# schimmeliger_keller.net
KiCad netlist of a schematic drawn in EAGLE
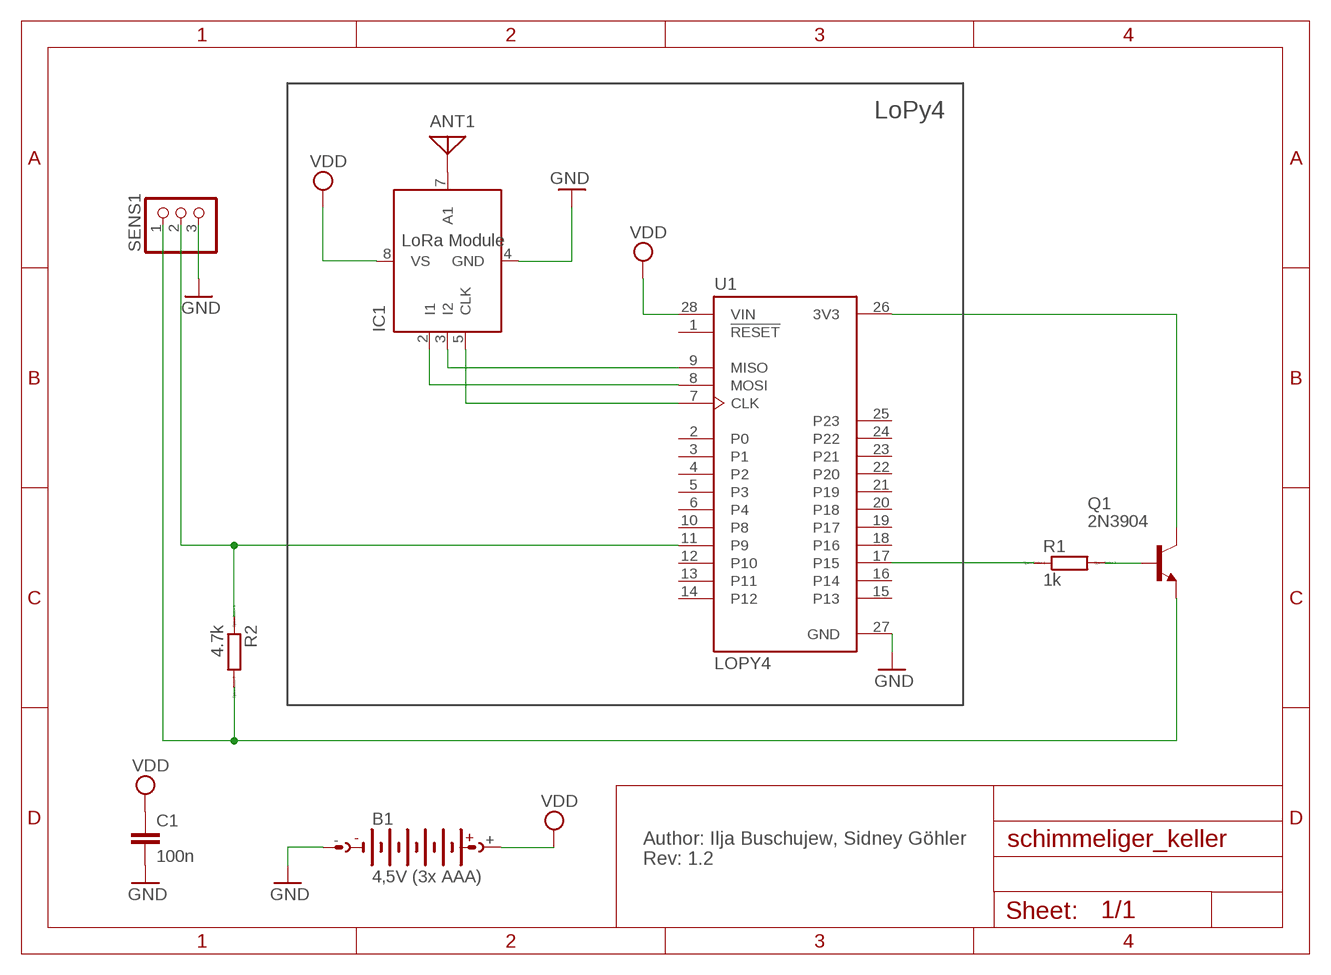
[diagram p0: schematic, sheet 1]

(export (version "E")
  (design (tool "Eeschema 10.0.6"))
  (components
    (comp (ref "ANT1")
      (value "ANTENNA")
      (footprint "eagle-import:PAD-01")
      (libsource (lib "eagle-import") (part "ANTENNA"))
    )
    (comp (ref "B1")
      (value "4,5V (3x AAA)")
      (footprint "eagle-import:AB9V")
      (libsource (lib "eagle-import") (part "AB9V"))
    )
    (comp (ref "C1")
      (value "100n")
      (footprint "eagle-import:C10B4")
      (libsource (lib "eagle-import") (part "C10/4"))
    )
    (comp (ref "IC1")
      (value "LoRa Module")
      (footprint "eagle-import:DIL08")
      (libsource (lib "eagle-import") (part "U893BSE"))
    )
    (comp (ref "Q1")
      (value "2N3904")
      (footprint "eagle-import:TO92")
      (libsource (lib "eagle-import") (part "2N3904"))
    )
    (comp (ref "R1")
      (value "1k")
      (footprint "eagle-import:0204_7")
      (libsource (lib "eagle-import") (part "R0204/7"))
    )
    (comp (ref "R2")
      (value "4.7k")
      (footprint "eagle-import:0204_7")
      (libsource (lib "eagle-import") (part "R0204/7"))
    )
    (comp (ref "SENS1")
      (value "PINHD-1X3")
      (footprint "eagle-import:1X03")
      (libsource (lib "eagle-import") (part "PINHD-1X3"))
    )
    (comp (ref "U1")
      (value "LOPY4")
      (footprint "eagle-import:MODULE_LOPY4")
      (fields (field (name "MF") "Pycom Ltd."))
      (libsource (lib "eagle-import") (part "LOPY4"))
    )
  )
  (nets
    (net (code "1") (name "GND") (class "Default")
      (node (ref "B1") (pin "-") (pinfunction "-_-") (pintype "passive"))
      (node (ref "C1") (pin "2") (pinfunction "2_2") (pintype "passive"))
      (node (ref "IC1") (pin "4") (pinfunction "GND_4") (pintype "power_in"))
      (node (ref "SENS1") (pin "3") (pinfunction "3_3") (pintype "passive"))
      (node (ref "U1") (pin "27") (pinfunction "GND_27") (pintype "power_in"))
    )
    (net (code "2") (name "Net-(IC1-A1)") (class "Default")
      (node (ref "ANT1") (pin "1") (pinfunction "1_1") (pintype "output"))
      (node (ref "IC1") (pin "7") (pinfunction "A1_7") (pintype "output"))
    )
    (net (code "3") (name "Net-(IC1-CLK)") (class "Default")
      (node (ref "IC1") (pin "5") (pinfunction "CLK_5") (pintype "input"))
      (node (ref "U1") (pin "7") (pinfunction "CLK_7") (pintype "output"))
    )
    (net (code "4") (name "Net-(IC1-I1)") (class "Default")
      (node (ref "IC1") (pin "2") (pinfunction "I1_2") (pintype "input"))
      (node (ref "U1") (pin "8") (pinfunction "MOSI_8") (pintype "output"))
    )
    (net (code "5") (name "Net-(IC1-I2)") (class "Default")
      (node (ref "IC1") (pin "3") (pinfunction "I2_3") (pintype "input"))
      (node (ref "U1") (pin "9") (pinfunction "MISO_9") (pintype "input"))
    )
    (net (code "6") (name "Net-(Q1-B)") (class "Default")
      (node (ref "Q1") (pin "2") (pinfunction "B_2") (pintype "passive"))
      (node (ref "R1") (pin "2") (pinfunction "2_2") (pintype "passive"))
    )
    (net (code "7") (name "Net-(Q1-C)") (class "Default")
      (node (ref "Q1") (pin "1") (pinfunction "C_1") (pintype "passive"))
      (node (ref "U1") (pin "26") (pinfunction "3V3_26") (pintype "output"))
    )
    (net (code "8") (name "Net-(Q1-E)") (class "Default")
      (node (ref "Q1") (pin "3") (pinfunction "E_3") (pintype "passive"))
      (node (ref "R2") (pin "2") (pinfunction "2_2") (pintype "passive"))
      (node (ref "SENS1") (pin "1") (pinfunction "1_1") (pintype "passive"))
    )
    (net (code "9") (name "Net-(U1-P9)") (class "Default")
      (node (ref "R2") (pin "1") (pinfunction "1_1") (pintype "passive"))
      (node (ref "SENS1") (pin "2") (pinfunction "2_2") (pintype "passive"))
      (node (ref "U1") (pin "11") (pinfunction "P9_11") (pintype "bidirectional"))
    )
    (net (code "10") (name "Net-(U1-P15)") (class "Default")
      (node (ref "R1") (pin "1") (pinfunction "1_1") (pintype "passive"))
      (node (ref "U1") (pin "17") (pinfunction "P15_17") (pintype "input"))
    )
    (net (code "11") (name "VDD") (class "Default")
      (node (ref "B1") (pin "+") (pinfunction "+_+") (pintype "passive"))
      (node (ref "C1") (pin "1") (pinfunction "1_1") (pintype "passive"))
      (node (ref "IC1") (pin "8") (pinfunction "VS_8") (pintype "power_in"))
      (node (ref "U1") (pin "28") (pinfunction "VIN_28") (pintype "input"))
    )
    (net (code "12") (name "unconnected-(U1-P0-Pad2)") (class "Default")
      (node (ref "U1") (pin "2") (pinfunction "P0_2") (pintype "bidirectional"))
    )
    (net (code "13") (name "unconnected-(U1-P1-Pad3)") (class "Default")
      (node (ref "U1") (pin "3") (pinfunction "P1_3") (pintype "bidirectional"))
    )
    (net (code "14") (name "unconnected-(U1-P2-Pad4)") (class "Default")
      (node (ref "U1") (pin "4") (pinfunction "P2_4") (pintype "bidirectional"))
    )
    (net (code "15") (name "unconnected-(U1-P3-Pad5)") (class "Default")
      (node (ref "U1") (pin "5") (pinfunction "P3_5") (pintype "bidirectional"))
    )
    (net (code "16") (name "unconnected-(U1-P4-Pad6)") (class "Default")
      (node (ref "U1") (pin "6") (pinfunction "P4_6") (pintype "bidirectional"))
    )
    (net (code "17") (name "unconnected-(U1-P8-Pad10)") (class "Default")
      (node (ref "U1") (pin "10") (pinfunction "P8_10") (pintype "bidirectional"))
    )
    (net (code "18") (name "unconnected-(U1-P10-Pad12)") (class "Default")
      (node (ref "U1") (pin "12") (pinfunction "P10_12") (pintype "bidirectional"))
    )
    (net (code "19") (name "unconnected-(U1-P11-Pad13)") (class "Default")
      (node (ref "U1") (pin "13") (pinfunction "P11_13") (pintype "bidirectional"))
    )
    (net (code "20") (name "unconnected-(U1-P12-Pad14)") (class "Default")
      (node (ref "U1") (pin "14") (pinfunction "P12_14") (pintype "bidirectional"))
    )
    (net (code "21") (name "unconnected-(U1-P13-Pad15)") (class "Default")
      (node (ref "U1") (pin "15") (pinfunction "P13_15") (pintype "input"))
    )
    (net (code "22") (name "unconnected-(U1-P14-Pad16)") (class "Default")
      (node (ref "U1") (pin "16") (pinfunction "P14_16") (pintype "input"))
    )
    (net (code "23") (name "unconnected-(U1-P16-Pad18)") (class "Default")
      (node (ref "U1") (pin "18") (pinfunction "P16_18") (pintype "input"))
    )
    (net (code "24") (name "unconnected-(U1-P17-Pad19)") (class "Default")
      (node (ref "U1") (pin "19") (pinfunction "P17_19") (pintype "input"))
    )
    (net (code "25") (name "unconnected-(U1-P18-Pad20)") (class "Default")
      (node (ref "U1") (pin "20") (pinfunction "P18_20") (pintype "input"))
    )
    (net (code "26") (name "unconnected-(U1-P19-Pad21)") (class "Default")
      (node (ref "U1") (pin "21") (pinfunction "P19_21") (pintype "bidirectional"))
    )
    (net (code "27") (name "unconnected-(U1-P20-Pad22)") (class "Default")
      (node (ref "U1") (pin "22") (pinfunction "P20_22") (pintype "bidirectional"))
    )
    (net (code "28") (name "unconnected-(U1-P21-Pad23)") (class "Default")
      (node (ref "U1") (pin "23") (pinfunction "P21_23") (pintype "bidirectional"))
    )
    (net (code "29") (name "unconnected-(U1-P22-Pad24)") (class "Default")
      (node (ref "U1") (pin "24") (pinfunction "P22_24") (pintype "bidirectional"))
    )
    (net (code "30") (name "unconnected-(U1-P23-Pad25)") (class "Default")
      (node (ref "U1") (pin "25") (pinfunction "P23_25") (pintype "bidirectional"))
    )
    (net (code "31") (name "unconnected-(U1-~{RESET}-Pad1)") (class "Default")
      (node (ref "U1") (pin "1") (pinfunction "~{RESET}_1") (pintype "input"))
    )
  )
)
